# untitled.net
KiCad netlist of a schematic drawn in EAGLE
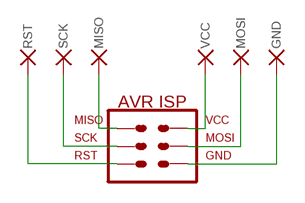
[diagram p0: schematic, sheet 1]

(export (version "E")
  (design (tool "Eeschema 10.0.6"))
  (components
    (comp (ref "GND")
      (value "GND")
      (footprint "eagle-import:POGO_PIN_P75-XX_HORIZONTALLY")
      (libsource (lib "eagle-import") (part "POGO_PIN_P75-XX_HORIZONTALLY"))
    )
    (comp (ref "MISO")
      (value "MISO")
      (footprint "eagle-import:POGO_PIN_P75-XX_HORIZONTALLY")
      (libsource (lib "eagle-import") (part "POGO_PIN_P75-XX_HORIZONTALLY"))
    )
    (comp (ref "MOSI")
      (value "MOSI")
      (footprint "eagle-import:POGO_PIN_P75-XX_HORIZONTALLY")
      (libsource (lib "eagle-import") (part "POGO_PIN_P75-XX_HORIZONTALLY"))
    )
    (comp (ref "RST")
      (value "RST")
      (footprint "eagle-import:POGO_PIN_P75-XX_HORIZONTALLY")
      (libsource (lib "eagle-import") (part "POGO_PIN_P75-XX_HORIZONTALLY"))
    )
    (comp (ref "SCK")
      (value "SCK")
      (footprint "eagle-import:POGO_PIN_P75-XX_HORIZONTALLY")
      (libsource (lib "eagle-import") (part "POGO_PIN_P75-XX_HORIZONTALLY"))
    )
    (comp (ref "VCC")
      (value "VCC")
      (footprint "eagle-import:POGO_PIN_P75-XX_HORIZONTALLY")
      (libsource (lib "eagle-import") (part "POGO_PIN_P75-XX_HORIZONTALLY"))
    )
    (comp (ref "X1")
      (value "AVR-ISP_6X_IDC_LOCK_EDGE_PCB")
      (footprint "eagle-import:AVR-ISP-6_EDGE_PCB")
      (libsource (lib "eagle-import") (part "AVR-ISP_6X_IDC_LOCK_EDGE_PCB"))
    )
  )
  (nets
    (net (code "1") (name "Net-(GND-P)") (class "Default")
      (node (ref "GND") (pin "P$1") (pinfunction "P_P$1") (pintype "passive"))
      (node (ref "X1") (pin "GND") (pinfunction "GND_GND") (pintype "passive"))
    )
    (net (code "2") (name "Net-(MISO-P)") (class "Default")
      (node (ref "MISO") (pin "P$1") (pinfunction "P_P$1") (pintype "passive"))
      (node (ref "X1") (pin "MISO") (pinfunction "MISO_MISO") (pintype "passive"))
    )
    (net (code "3") (name "Net-(MOSI-P)") (class "Default")
      (node (ref "MOSI") (pin "P$1") (pinfunction "P_P$1") (pintype "passive"))
      (node (ref "X1") (pin "MOSI") (pinfunction "MOSI_MOSI") (pintype "passive"))
    )
    (net (code "4") (name "Net-(RST-P)") (class "Default")
      (node (ref "RST") (pin "P$1") (pinfunction "P_P$1") (pintype "passive"))
      (node (ref "X1") (pin "RST") (pinfunction "RST_RST") (pintype "passive"))
    )
    (net (code "5") (name "Net-(SCK-P)") (class "Default")
      (node (ref "SCK") (pin "P$1") (pinfunction "P_P$1") (pintype "passive"))
      (node (ref "X1") (pin "SCK") (pinfunction "SCK_SCK") (pintype "passive"))
    )
    (net (code "6") (name "Net-(VCC-P)") (class "Default")
      (node (ref "VCC") (pin "P$1") (pinfunction "P_P$1") (pintype "passive"))
      (node (ref "X1") (pin "VCC") (pinfunction "VCC_VCC") (pintype "passive"))
    )
  )
)
